# circuit.net
KiCad netlist of a schematic drawn in EAGLE
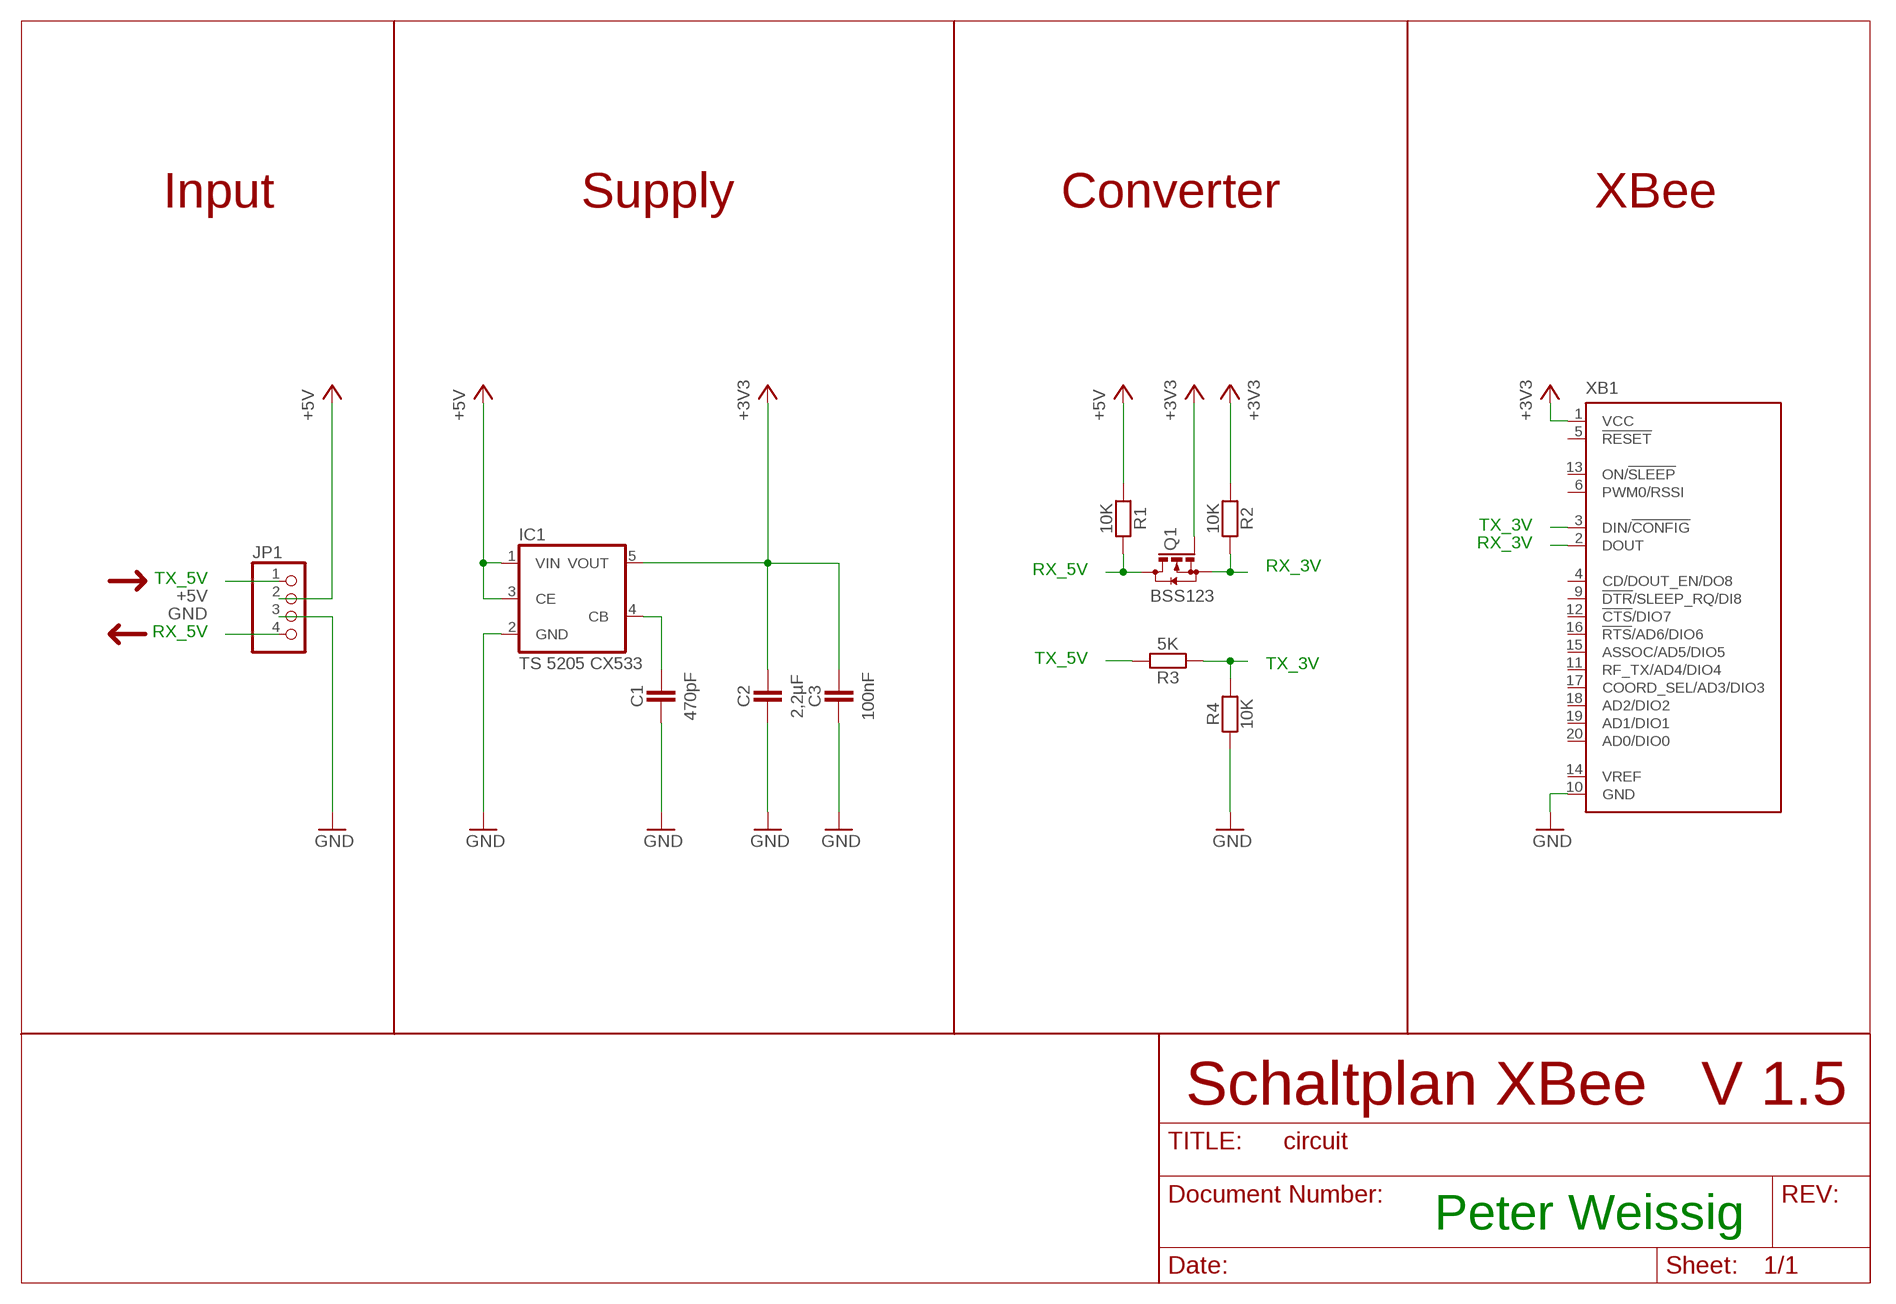
[diagram p0: schematic, sheet 1]

(export (version "E")
  (design (tool "Eeschema 10.0.6"))
  (components
    (comp (ref "C1")
      (value "470pF")
      (footprint "eagle-import:SMD_1206")
      (libsource (lib "eagle-import") (part "CAPACITATOR-1206"))
    )
    (comp (ref "C2")
      (value "2,2µF")
      (footprint "eagle-import:SMD_1206")
      (libsource (lib "eagle-import") (part "CAPACITATOR-1206"))
    )
    (comp (ref "C3")
      (value "100nF")
      (footprint "eagle-import:SMD_1206")
      (libsource (lib "eagle-import") (part "CAPACITATOR-1206"))
    )
    (comp (ref "IC1")
      (value "TS 5205 CX533")
      (footprint "eagle-import:SOT25")
      (libsource (lib "eagle-import") (part "TS520533"))
    )
    (comp (ref "JP1")
      (value "PINHD-1X4")
      (footprint "eagle-import:1X04")
      (libsource (lib "eagle-import") (part "PINHD-1X4"))
    )
    (comp (ref "Q1")
      (value "BSS123")
      (footprint "eagle-import:SOT23")
      (libsource (lib "eagle-import") (part "BSS123"))
    )
    (comp (ref "R1")
      (value "10K")
      (footprint "eagle-import:SMD_1206")
      (libsource (lib "eagle-import") (part "RESISTOR-1206"))
    )
    (comp (ref "R2")
      (value "10K")
      (footprint "eagle-import:SMD_1206")
      (libsource (lib "eagle-import") (part "RESISTOR-1206"))
    )
    (comp (ref "R3")
      (value "5K")
      (footprint "eagle-import:SMD_1206")
      (libsource (lib "eagle-import") (part "RESISTOR-1206"))
    )
    (comp (ref "R4")
      (value "10K")
      (footprint "eagle-import:SMD_1206")
      (libsource (lib "eagle-import") (part "RESISTOR-1206"))
    )
    (comp (ref "XB1")
      (value "XBEESMD")
      (footprint "eagle-import:FUNK_XBEE2")
      (libsource (lib "eagle-import") (part "XBEESMD"))
    )
  )
  (nets
    (net (code "1") (name "+3V3") (class "Default")
      (node (ref "C2") (pin "1") (pinfunction "1_1") (pintype "passive"))
      (node (ref "C3") (pin "1") (pinfunction "1_1") (pintype "passive"))
      (node (ref "IC1") (pin "5") (pinfunction "VOUT_5") (pintype "passive"))
      (node (ref "Q1") (pin "1") (pinfunction "G_1") (pintype "passive"))
      (node (ref "R2") (pin "2") (pinfunction "P2_2") (pintype "passive"))
      (node (ref "XB1") (pin "1") (pinfunction "VCC_1") (pintype "power_in"))
    )
    (net (code "2") (name "+5V") (class "Default")
      (node (ref "IC1") (pin "1") (pinfunction "VIN_1") (pintype "input"))
      (node (ref "IC1") (pin "3") (pinfunction "CE_3") (pintype "input"))
      (node (ref "JP1") (pin "2") (pinfunction "2_2") (pintype "passive"))
      (node (ref "R1") (pin "2") (pinfunction "P2_2") (pintype "passive"))
    )
    (net (code "3") (name "/RX_3V") (class "Default")
      (node (ref "Q1") (pin "2") (pinfunction "S_2") (pintype "passive"))
      (node (ref "R2") (pin "1") (pinfunction "P1_1") (pintype "passive"))
      (node (ref "XB1") (pin "2") (pinfunction "DOUT_2") (pintype "output"))
    )
    (net (code "4") (name "/RX_5V") (class "Default")
      (node (ref "JP1") (pin "4") (pinfunction "4_4") (pintype "passive"))
      (node (ref "Q1") (pin "3") (pinfunction "D_3") (pintype "passive"))
      (node (ref "R1") (pin "1") (pinfunction "P1_1") (pintype "passive"))
    )
    (net (code "5") (name "/TX_3V") (class "Default")
      (node (ref "R3") (pin "2") (pinfunction "P2_2") (pintype "passive"))
      (node (ref "R4") (pin "1") (pinfunction "P1_1") (pintype "passive"))
      (node (ref "XB1") (pin "3") (pinfunction "DIN/~{CONFIG}_3") (pintype "input"))
    )
    (net (code "6") (name "/TX_5V") (class "Default")
      (node (ref "JP1") (pin "1") (pinfunction "1_1") (pintype "passive"))
      (node (ref "R3") (pin "1") (pinfunction "P1_1") (pintype "passive"))
    )
    (net (code "7") (name "GND") (class "Default")
      (node (ref "C1") (pin "2") (pinfunction "2_2") (pintype "passive"))
      (node (ref "C2") (pin "2") (pinfunction "2_2") (pintype "passive"))
      (node (ref "C3") (pin "2") (pinfunction "2_2") (pintype "passive"))
      (node (ref "IC1") (pin "2") (pinfunction "GND_2") (pintype "passive"))
      (node (ref "JP1") (pin "3") (pinfunction "3_3") (pintype "passive"))
      (node (ref "R4") (pin "2") (pinfunction "P2_2") (pintype "passive"))
      (node (ref "XB1") (pin "10") (pinfunction "GND_10") (pintype "power_in"))
    )
    (net (code "8") (name "Net-(IC1-CB)") (class "Default")
      (node (ref "C1") (pin "1") (pinfunction "1_1") (pintype "passive"))
      (node (ref "IC1") (pin "4") (pinfunction "CB_4") (pintype "input"))
    )
    (net (code "9") (name "unconnected-(XB1-AD0{slash}DIO0-Pad20)") (class "Default")
      (node (ref "XB1") (pin "20") (pinfunction "AD0/DIO0_20") (pintype "bidirectional"))
    )
    (net (code "10") (name "unconnected-(XB1-AD1{slash}DIO1-Pad19)") (class "Default")
      (node (ref "XB1") (pin "19") (pinfunction "AD1/DIO1_19") (pintype "bidirectional"))
    )
    (net (code "11") (name "unconnected-(XB1-AD2{slash}DIO2-Pad18)") (class "Default")
      (node (ref "XB1") (pin "18") (pinfunction "AD2/DIO2_18") (pintype "bidirectional"))
    )
    (net (code "12") (name "unconnected-(XB1-ASSOC{slash}AD5{slash}DIO5-Pad15)") (class "Default")
      (node (ref "XB1") (pin "15") (pinfunction "ASSOC/AD5/DIO5_15") (pintype "bidirectional"))
    )
    (net (code "13") (name "unconnected-(XB1-CD{slash}DOUT_EN{slash}DO8-Pad4)") (class "Default")
      (node (ref "XB1") (pin "4") (pinfunction "CD/DOUT_EN/DO8_4") (pintype "output"))
    )
    (net (code "14") (name "unconnected-(XB1-COORD_SEL{slash}AD3{slash}DIO3-Pad17)") (class "Default")
      (node (ref "XB1") (pin "17") (pinfunction "COORD_SEL/AD3/DIO3_17") (pintype "bidirectional"))
    )
    (net (code "15") (name "unconnected-(XB1-ON{slash}~{SLEEP}-Pad13)") (class "Default")
      (node (ref "XB1") (pin "13") (pinfunction "ON/~{SLEEP}_13") (pintype "output"))
    )
    (net (code "16") (name "unconnected-(XB1-PWM0{slash}RSSI-Pad6)") (class "Default")
      (node (ref "XB1") (pin "6") (pinfunction "PWM0/RSSI_6") (pintype "output"))
    )
    (net (code "17") (name "unconnected-(XB1-RF_TX{slash}AD4{slash}DIO4-Pad11)") (class "Default")
      (node (ref "XB1") (pin "11") (pinfunction "RF_TX/AD4/DIO4_11") (pintype "bidirectional"))
    )
    (net (code "18") (name "unconnected-(XB1-VREF-Pad14)") (class "Default")
      (node (ref "XB1") (pin "14") (pinfunction "VREF_14") (pintype "input"))
    )
    (net (code "19") (name "unconnected-(XB1-~{CTS}{slash}DIO7-Pad12)") (class "Default")
      (node (ref "XB1") (pin "12") (pinfunction "~{CTS}/DIO7_12") (pintype "bidirectional"))
    )
    (net (code "20") (name "unconnected-(XB1-~{DTR}{slash}SLEEP_RQ{slash}DI8-Pad9)") (class "Default")
      (node (ref "XB1") (pin "9") (pinfunction "~{DTR}/SLEEP_RQ/DI8_9") (pintype "bidirectional"))
    )
    (net (code "21") (name "unconnected-(XB1-~{RESET}-Pad5)") (class "Default")
      (node (ref "XB1") (pin "5") (pinfunction "~{RESET}_5") (pintype "input"))
    )
    (net (code "22") (name "unconnected-(XB1-~{RTS}{slash}AD6{slash}DIO6-Pad16)") (class "Default")
      (node (ref "XB1") (pin "16") (pinfunction "~{RTS}/AD6/DIO6_16") (pintype "bidirectional"))
    )
  )
)
